# VinoTemp.net
KiCad netlist of a schematic drawn in EAGLE
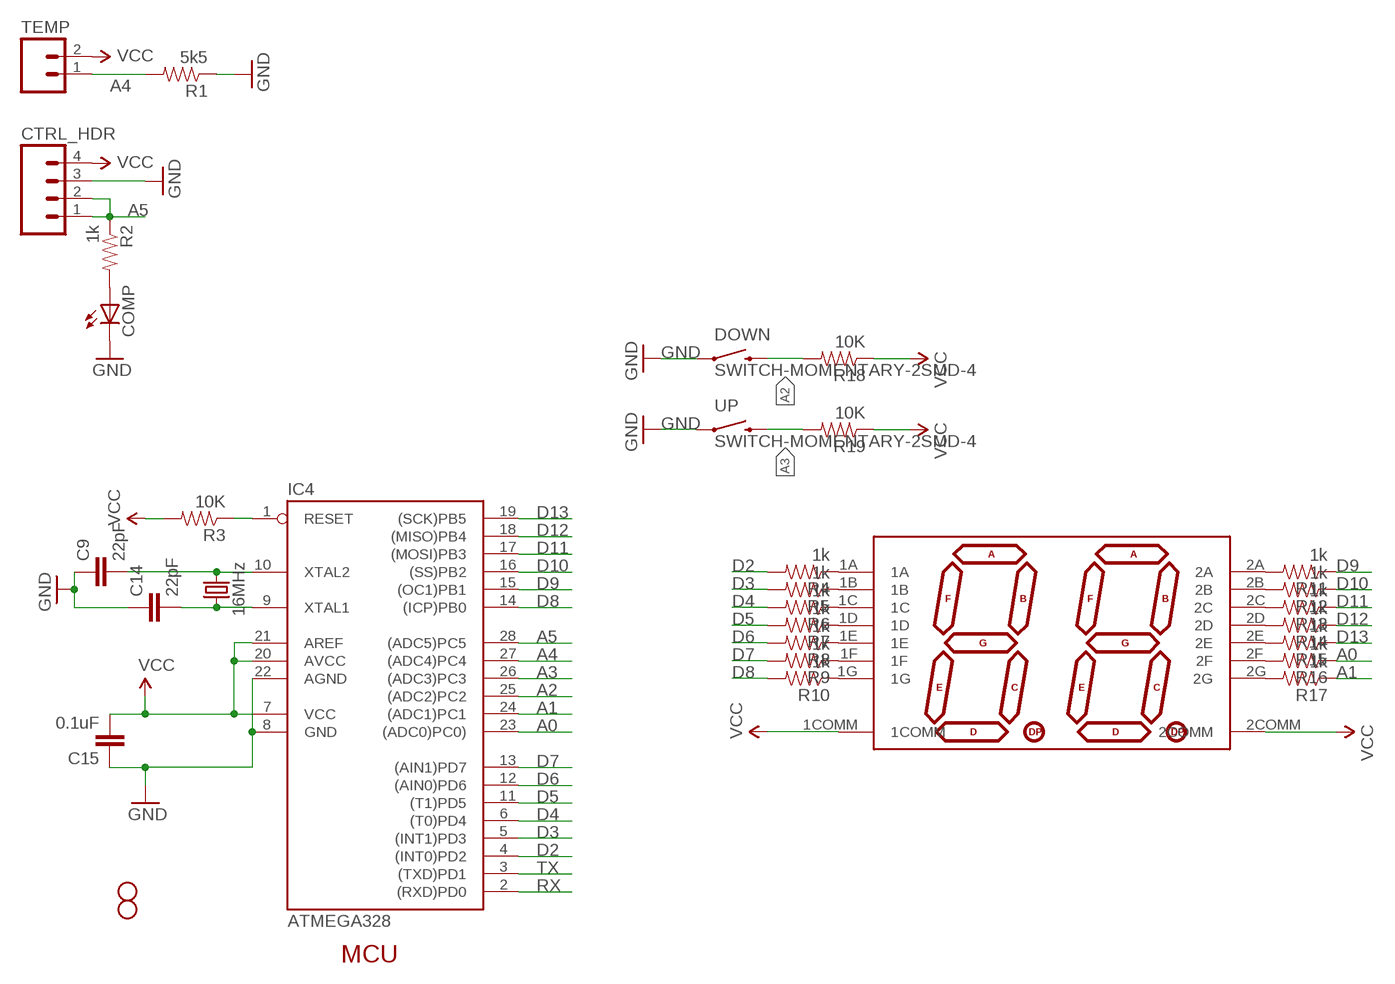
[diagram p0: schematic, sheet 1]

(export (version "E")
  (design (tool "Eeschema 10.0.6"))
  (components
    (comp (ref "C9")
      (value "22pF")
      (footprint "eagle-import:CAP-PTH-SMALL2")
      (libsource (lib "eagle-import") (part "CAPPTH2"))
    )
    (comp (ref "C14")
      (value "22pF")
      (footprint "eagle-import:CAP-PTH-SMALL2")
      (libsource (lib "eagle-import") (part "CAPPTH2"))
    )
    (comp (ref "C15")
      (value "0.1uF")
      (footprint "eagle-import:CAP-PTH-SMALL2")
      (libsource (lib "eagle-import") (part "CAPPTH2"))
    )
    (comp (ref "COMP")
      (value "LED3MM")
      (footprint "eagle-import:LED3MM")
      (libsource (lib "eagle-import") (part "LED3MM"))
    )
    (comp (ref "CTRL_HDR")
      (value "M04POLAR")
      (footprint "eagle-import:MOLEX-1X4")
      (libsource (lib "eagle-import") (part "M04POLAR"))
    )
    (comp (ref "DOWN")
      (value "SWITCH-MOMENTARY-2SMD-4")
      (footprint "eagle-import:TACTILE_SWITCH_TALL")
      (libsource (lib "eagle-import") (part "SWITCH-MOMENTARY-2SMD-4"))
    )
    (comp (ref "IC4")
      (value "ATMEGA328")
      (footprint "eagle-import:DIL28-3")
      (libsource (lib "eagle-import") (part "AT90S4433P"))
    )
    (comp (ref "JP2")
      (value "STAND-OFF#2")
      (footprint "eagle-import:STAND-OFF-#2")
      (libsource (lib "eagle-import") (part "STAND-OFF#2"))
    )
    (comp (ref "JP6")
      (value "STAND-OFF#2")
      (footprint "eagle-import:STAND-OFF-#2")
      (libsource (lib "eagle-import") (part "STAND-OFF#2"))
    )
    (comp (ref "R1")
      (value "5k5")
      (footprint "eagle-import:AXIAL-0.3")
      (libsource (lib "eagle-import") (part "RESISTORAXIAL-0.3"))
    )
    (comp (ref "R2")
      (value "1k")
      (footprint "eagle-import:0805")
      (libsource (lib "eagle-import") (part "SparkFun-Resistors_RESISTOR0805-RES"))
    )
    (comp (ref "R3")
      (value "10K")
      (footprint "eagle-import:0805")
      (libsource (lib "eagle-import") (part "SparkFun-Resistors_RESISTOR0805-RES"))
    )
    (comp (ref "R4")
      (value "1k")
      (footprint "eagle-import:0805")
      (libsource (lib "eagle-import") (part "SparkFun-Resistors_RESISTOR0805-RES"))
    )
    (comp (ref "R5")
      (value "1k")
      (footprint "eagle-import:0805")
      (libsource (lib "eagle-import") (part "SparkFun-Resistors_RESISTOR0805-RES"))
    )
    (comp (ref "R6")
      (value "1k")
      (footprint "eagle-import:0805")
      (libsource (lib "eagle-import") (part "SparkFun-Resistors_RESISTOR0805-RES"))
    )
    (comp (ref "R7")
      (value "1k")
      (footprint "eagle-import:0805")
      (libsource (lib "eagle-import") (part "SparkFun-Resistors_RESISTOR0805-RES"))
    )
    (comp (ref "R8")
      (value "1k")
      (footprint "eagle-import:0805")
      (libsource (lib "eagle-import") (part "SparkFun-Resistors_RESISTOR0805-RES"))
    )
    (comp (ref "R9")
      (value "1k")
      (footprint "eagle-import:0805")
      (libsource (lib "eagle-import") (part "SparkFun-Resistors_RESISTOR0805-RES"))
    )
    (comp (ref "R10")
      (value "1k")
      (footprint "eagle-import:0805")
      (libsource (lib "eagle-import") (part "SparkFun-Resistors_RESISTOR0805-RES"))
    )
    (comp (ref "R11")
      (value "1k")
      (footprint "eagle-import:0805")
      (libsource (lib "eagle-import") (part "SparkFun-Resistors_RESISTOR0805-RES"))
    )
    (comp (ref "R12")
      (value "1k")
      (footprint "eagle-import:0805")
      (libsource (lib "eagle-import") (part "SparkFun-Resistors_RESISTOR0805-RES"))
    )
    (comp (ref "R13")
      (value "1k")
      (footprint "eagle-import:0805")
      (libsource (lib "eagle-import") (part "SparkFun-Resistors_RESISTOR0805-RES"))
    )
    (comp (ref "R14")
      (value "1k")
      (footprint "eagle-import:0805")
      (libsource (lib "eagle-import") (part "SparkFun-Resistors_RESISTOR0805-RES"))
    )
    (comp (ref "R15")
      (value "1k")
      (footprint "eagle-import:0805")
      (libsource (lib "eagle-import") (part "SparkFun-Resistors_RESISTOR0805-RES"))
    )
    (comp (ref "R16")
      (value "1k")
      (footprint "eagle-import:0805")
      (libsource (lib "eagle-import") (part "SparkFun-Resistors_RESISTOR0805-RES"))
    )
    (comp (ref "R17")
      (value "1k")
      (footprint "eagle-import:0805")
      (libsource (lib "eagle-import") (part "SparkFun-Resistors_RESISTOR0805-RES"))
    )
    (comp (ref "R18")
      (value "10K")
      (footprint "eagle-import:0805")
      (libsource (lib "eagle-import") (part "SparkFun-Resistors_RESISTOR0805-RES"))
    )
    (comp (ref "R19")
      (value "10K")
      (footprint "eagle-import:0805")
      (libsource (lib "eagle-import") (part "SparkFun-Resistors_RESISTOR0805-RES"))
    )
    (comp (ref "TEMP")
      (value "M02POLAR")
      (footprint "eagle-import:MOLEX-1X2")
      (libsource (lib "eagle-import") (part "M02POLAR"))
    )
    (comp (ref "U$1")
      (value "7-SEGMENT-DISPLAY-2-DIGITPTH")
      (footprint "eagle-import:7-SEGMENT-DISPLAY-2-DIGIT-KINGBRIGHT-DA04")
      (libsource (lib "eagle-import") (part "7-SEGMENT-DISPLAY-2-DIGITPTH"))
    )
    (comp (ref "UP")
      (value "SWITCH-MOMENTARY-2SMD-4")
      (footprint "eagle-import:TACTILE_SWITCH_TALL")
      (libsource (lib "eagle-import") (part "SWITCH-MOMENTARY-2SMD-4"))
    )
    (comp (ref "Y1")
      (value "16MHz")
      (footprint "eagle-import:HC49US")
      (libsource (lib "eagle-import") (part "CRYSTALHC49US"))
    )
  )
  (nets
    (net (code "1") (name "/A0") (class "Default")
      (node (ref "IC4") (pin "23") (pinfunction "(ADC0)PC0)_23") (pintype "bidirectional"))
      (node (ref "R16") (pin "1") (pinfunction "1_1") (pintype "passive"))
    )
    (net (code "2") (name "/A1") (class "Default")
      (node (ref "IC4") (pin "24") (pinfunction "(ADC1)PC1_24") (pintype "bidirectional"))
      (node (ref "R17") (pin "1") (pinfunction "1_1") (pintype "passive"))
    )
    (net (code "3") (name "/A4") (class "Default")
      (node (ref "IC4") (pin "27") (pinfunction "(ADC4)PC4_27") (pintype "bidirectional"))
      (node (ref "R1") (pin "P$2") (pinfunction "2_P$2") (pintype "passive"))
      (node (ref "TEMP") (pin "1") (pinfunction "1_1") (pintype "passive"))
    )
    (net (code "4") (name "/A5") (class "Default")
      (node (ref "CTRL_HDR") (pin "1") (pinfunction "1_1") (pintype "passive"))
      (node (ref "CTRL_HDR") (pin "2") (pinfunction "2_2") (pintype "passive"))
      (node (ref "IC4") (pin "28") (pinfunction "(ADC5)PC5_28") (pintype "bidirectional"))
      (node (ref "R2") (pin "1") (pinfunction "1_1") (pintype "passive"))
    )
    (net (code "5") (name "/D2") (class "Default")
      (node (ref "IC4") (pin "4") (pinfunction "(INT0)PD2_4") (pintype "bidirectional"))
      (node (ref "R4") (pin "2") (pinfunction "2_2") (pintype "passive"))
    )
    (net (code "6") (name "/D3") (class "Default")
      (node (ref "IC4") (pin "5") (pinfunction "(INT1)PD3_5") (pintype "bidirectional"))
      (node (ref "R5") (pin "2") (pinfunction "2_2") (pintype "passive"))
    )
    (net (code "7") (name "/D4") (class "Default")
      (node (ref "IC4") (pin "6") (pinfunction "(T0)PD4_6") (pintype "bidirectional"))
      (node (ref "R6") (pin "2") (pinfunction "2_2") (pintype "passive"))
    )
    (net (code "8") (name "/D5") (class "Default")
      (node (ref "IC4") (pin "11") (pinfunction "(T1)PD5_11") (pintype "bidirectional"))
      (node (ref "R7") (pin "2") (pinfunction "2_2") (pintype "passive"))
    )
    (net (code "9") (name "/D6") (class "Default")
      (node (ref "IC4") (pin "12") (pinfunction "(AIN0)PD6_12") (pintype "bidirectional"))
      (node (ref "R8") (pin "2") (pinfunction "2_2") (pintype "passive"))
    )
    (net (code "10") (name "/D7") (class "Default")
      (node (ref "IC4") (pin "13") (pinfunction "(AIN1)PD7_13") (pintype "bidirectional"))
      (node (ref "R9") (pin "2") (pinfunction "2_2") (pintype "passive"))
    )
    (net (code "11") (name "/D8") (class "Default")
      (node (ref "IC4") (pin "14") (pinfunction "(ICP)PB0_14") (pintype "bidirectional"))
      (node (ref "R10") (pin "2") (pinfunction "2_2") (pintype "passive"))
    )
    (net (code "12") (name "/D9") (class "Default")
      (node (ref "IC4") (pin "15") (pinfunction "(OC1)PB1_15") (pintype "bidirectional"))
      (node (ref "R11") (pin "1") (pinfunction "1_1") (pintype "passive"))
    )
    (net (code "13") (name "/D10") (class "Default")
      (node (ref "IC4") (pin "16") (pinfunction "(SS)PB2_16") (pintype "bidirectional"))
      (node (ref "R12") (pin "1") (pinfunction "1_1") (pintype "passive"))
    )
    (net (code "14") (name "/D11") (class "Default")
      (node (ref "IC4") (pin "17") (pinfunction "(MOSI)PB3_17") (pintype "bidirectional"))
      (node (ref "R13") (pin "1") (pinfunction "1_1") (pintype "passive"))
    )
    (net (code "15") (name "/D12") (class "Default")
      (node (ref "IC4") (pin "18") (pinfunction "(MISO)PB4_18") (pintype "bidirectional"))
      (node (ref "R14") (pin "1") (pinfunction "1_1") (pintype "passive"))
    )
    (net (code "16") (name "/D13") (class "Default")
      (node (ref "IC4") (pin "19") (pinfunction "(SCK)PB5_19") (pintype "bidirectional"))
      (node (ref "R15") (pin "1") (pinfunction "1_1") (pintype "passive"))
    )
    (net (code "17") (name "/RX") (class "Default")
      (node (ref "IC4") (pin "2") (pinfunction "(RXD)PD0_2") (pintype "bidirectional"))
    )
    (net (code "18") (name "/TX") (class "Default")
      (node (ref "IC4") (pin "3") (pinfunction "(TXD)PD1_3") (pintype "bidirectional"))
    )
    (net (code "19") (name "A2") (class "Default")
      (node (ref "DOWN") (pin "B2") (pinfunction "2_B2") (pintype "passive"))
      (node (ref "IC4") (pin "25") (pinfunction "(ADC2)PC2_25") (pintype "bidirectional"))
      (node (ref "R18") (pin "2") (pinfunction "2_2") (pintype "passive"))
    )
    (net (code "20") (name "A3") (class "Default")
      (node (ref "IC4") (pin "26") (pinfunction "(ADC3)PC3_26") (pintype "bidirectional"))
      (node (ref "R19") (pin "2") (pinfunction "2_2") (pintype "passive"))
      (node (ref "UP") (pin "B2") (pinfunction "2_B2") (pintype "passive"))
    )
    (net (code "21") (name "GND") (class "Default")
      (node (ref "C14") (pin "1") (pinfunction "1_1") (pintype "passive"))
      (node (ref "C15") (pin "1") (pinfunction "1_1") (pintype "passive"))
      (node (ref "C9") (pin "1") (pinfunction "1_1") (pintype "passive"))
      (node (ref "COMP") (pin "K") (pinfunction "C_K") (pintype "passive"))
      (node (ref "CTRL_HDR") (pin "3") (pinfunction "3_3") (pintype "passive"))
      (node (ref "DOWN") (pin "A2") (pinfunction "1_A2") (pintype "passive"))
      (node (ref "IC4") (pin "22") (pinfunction "AGND_22") (pintype "power_in"))
      (node (ref "IC4") (pin "8") (pinfunction "GND_8") (pintype "power_in"))
      (node (ref "R1") (pin "P$1") (pinfunction "1_P$1") (pintype "passive"))
      (node (ref "UP") (pin "A2") (pinfunction "1_A2") (pintype "passive"))
    )
    (net (code "22") (name "Net-(COMP-PadA)") (class "Default")
      (node (ref "COMP") (pin "A") (pinfunction "A_A") (pintype "passive"))
      (node (ref "R2") (pin "2") (pinfunction "2_2") (pintype "passive"))
    )
    (net (code "23") (name "Net-(IC4-RESET)") (class "Default")
      (node (ref "IC4") (pin "1") (pinfunction "RESET_1") (pintype "input"))
      (node (ref "R3") (pin "1") (pinfunction "1_1") (pintype "passive"))
    )
    (net (code "24") (name "Net-(IC4-XTAL1)") (class "Default")
      (node (ref "C14") (pin "2") (pinfunction "2_2") (pintype "passive"))
      (node (ref "IC4") (pin "9") (pinfunction "XTAL1_9") (pintype "bidirectional"))
      (node (ref "Y1") (pin "1") (pinfunction "1_1") (pintype "passive"))
    )
    (net (code "25") (name "Net-(IC4-XTAL2)") (class "Default")
      (node (ref "C9") (pin "2") (pinfunction "2_2") (pintype "passive"))
      (node (ref "IC4") (pin "10") (pinfunction "XTAL2_10") (pintype "bidirectional"))
      (node (ref "Y1") (pin "2") (pinfunction "2_2") (pintype "passive"))
    )
    (net (code "26") (name "Net-(R4-Pad1)") (class "Default")
      (node (ref "R4") (pin "1") (pinfunction "1_1") (pintype "passive"))
      (node (ref "U$1") (pin "1A") (pinfunction "1A_1A") (pintype "bidirectional"))
    )
    (net (code "27") (name "Net-(R5-Pad1)") (class "Default")
      (node (ref "R5") (pin "1") (pinfunction "1_1") (pintype "passive"))
      (node (ref "U$1") (pin "1B") (pinfunction "1B_1B") (pintype "bidirectional"))
    )
    (net (code "28") (name "Net-(R6-Pad1)") (class "Default")
      (node (ref "R6") (pin "1") (pinfunction "1_1") (pintype "passive"))
      (node (ref "U$1") (pin "1C") (pinfunction "1C_1C") (pintype "bidirectional"))
    )
    (net (code "29") (name "Net-(R7-Pad1)") (class "Default")
      (node (ref "R7") (pin "1") (pinfunction "1_1") (pintype "passive"))
      (node (ref "U$1") (pin "1D") (pinfunction "1D_1D") (pintype "bidirectional"))
    )
    (net (code "30") (name "Net-(R8-Pad1)") (class "Default")
      (node (ref "R8") (pin "1") (pinfunction "1_1") (pintype "passive"))
      (node (ref "U$1") (pin "1E") (pinfunction "1E_1E") (pintype "bidirectional"))
    )
    (net (code "31") (name "Net-(R9-Pad1)") (class "Default")
      (node (ref "R9") (pin "1") (pinfunction "1_1") (pintype "passive"))
      (node (ref "U$1") (pin "1F") (pinfunction "1F_1F") (pintype "bidirectional"))
    )
    (net (code "32") (name "Net-(R10-Pad1)") (class "Default")
      (node (ref "R10") (pin "1") (pinfunction "1_1") (pintype "passive"))
      (node (ref "U$1") (pin "1G") (pinfunction "1G_1G") (pintype "bidirectional"))
    )
    (net (code "33") (name "Net-(R11-Pad2)") (class "Default")
      (node (ref "R11") (pin "2") (pinfunction "2_2") (pintype "passive"))
      (node (ref "U$1") (pin "2A") (pinfunction "2A_2A") (pintype "bidirectional"))
    )
    (net (code "34") (name "Net-(R12-Pad2)") (class "Default")
      (node (ref "R12") (pin "2") (pinfunction "2_2") (pintype "passive"))
      (node (ref "U$1") (pin "2B") (pinfunction "2B_2B") (pintype "bidirectional"))
    )
    (net (code "35") (name "Net-(R13-Pad2)") (class "Default")
      (node (ref "R13") (pin "2") (pinfunction "2_2") (pintype "passive"))
      (node (ref "U$1") (pin "2C") (pinfunction "2C_2C") (pintype "bidirectional"))
    )
    (net (code "36") (name "Net-(R14-Pad2)") (class "Default")
      (node (ref "R14") (pin "2") (pinfunction "2_2") (pintype "passive"))
      (node (ref "U$1") (pin "2D") (pinfunction "2D_2D") (pintype "bidirectional"))
    )
    (net (code "37") (name "Net-(R15-Pad2)") (class "Default")
      (node (ref "R15") (pin "2") (pinfunction "2_2") (pintype "passive"))
      (node (ref "U$1") (pin "2E") (pinfunction "2E_2E") (pintype "bidirectional"))
    )
    (net (code "38") (name "Net-(R16-Pad2)") (class "Default")
      (node (ref "R16") (pin "2") (pinfunction "2_2") (pintype "passive"))
      (node (ref "U$1") (pin "2F") (pinfunction "2F_2F") (pintype "bidirectional"))
    )
    (net (code "39") (name "Net-(R17-Pad2)") (class "Default")
      (node (ref "R17") (pin "2") (pinfunction "2_2") (pintype "passive"))
      (node (ref "U$1") (pin "2G") (pinfunction "2G_2G") (pintype "bidirectional"))
    )
    (net (code "40") (name "VCC") (class "Default")
      (node (ref "C15") (pin "2") (pinfunction "2_2") (pintype "passive"))
      (node (ref "CTRL_HDR") (pin "4") (pinfunction "4_4") (pintype "passive"))
      (node (ref "IC4") (pin "20") (pinfunction "AVCC_20") (pintype "power_in"))
      (node (ref "IC4") (pin "21") (pinfunction "AREF_21") (pintype "passive"))
      (node (ref "IC4") (pin "7") (pinfunction "VCC_7") (pintype "power_in"))
      (node (ref "R18") (pin "1") (pinfunction "1_1") (pintype "passive"))
      (node (ref "R19") (pin "1") (pinfunction "1_1") (pintype "passive"))
      (node (ref "R3") (pin "2") (pinfunction "2_2") (pintype "passive"))
      (node (ref "TEMP") (pin "2") (pinfunction "2_2") (pintype "passive"))
      (node (ref "U$1") (pin "1COMM") (pinfunction "1COMM_1COMM") (pintype "bidirectional"))
      (node (ref "U$1") (pin "2COMM") (pinfunction "2COMM_2COMM") (pintype "bidirectional"))
    )
  )
)
